# elm329.net
KiCad netlist of a schematic drawn in EAGLE
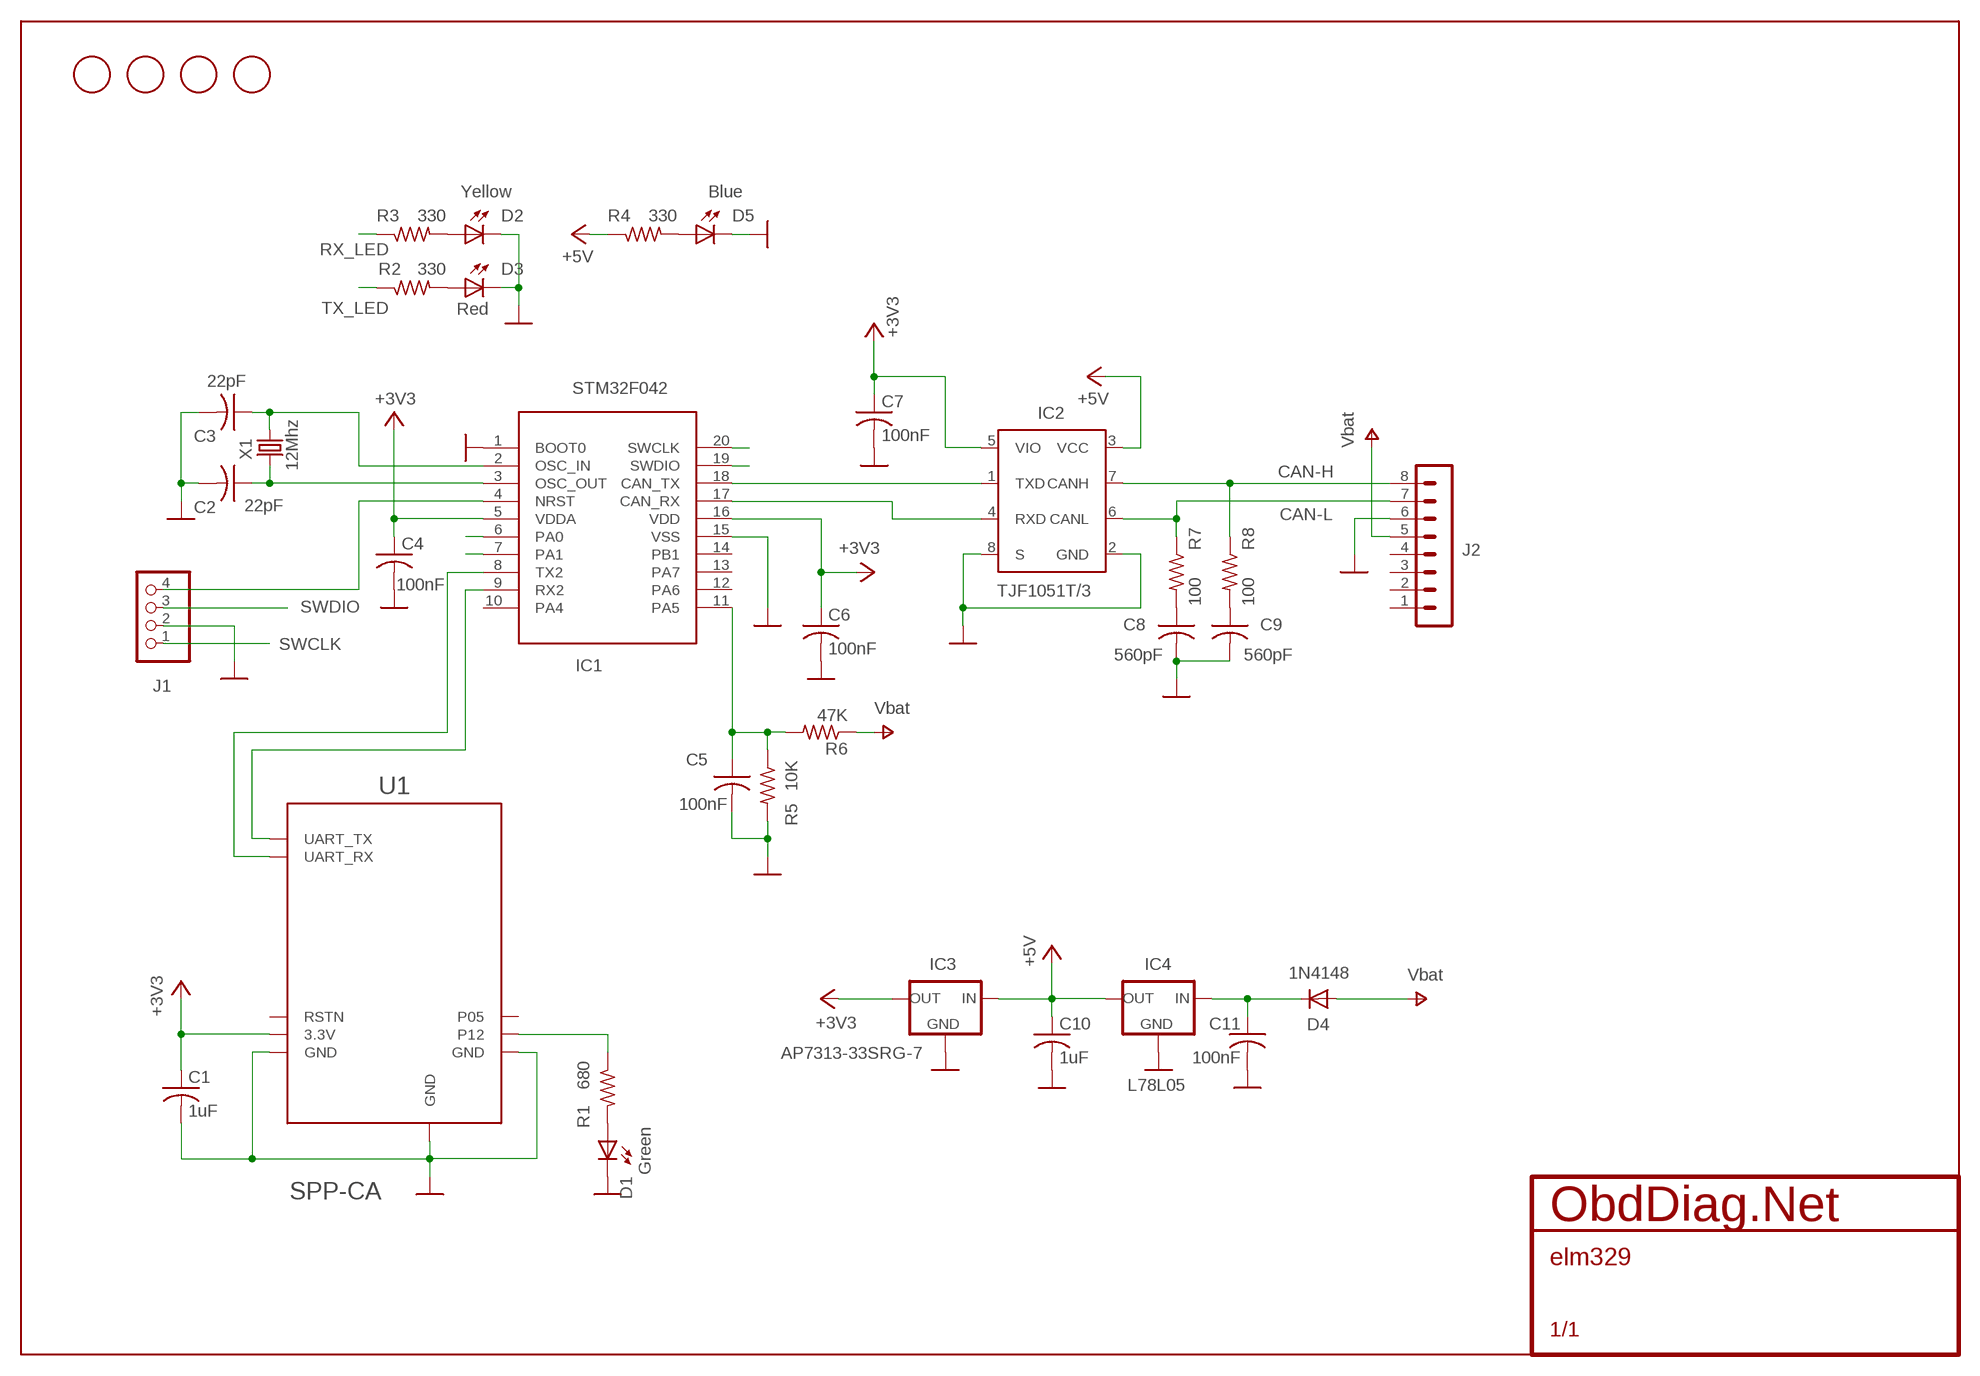
[diagram p0: schematic, sheet 1]

(export (version "E")
  (design (tool "Eeschema 10.0.6"))
  (components
    (comp (ref "C1")
      (value "1uF")
      (footprint "eagle-import:C0805")
      (libsource (lib "eagle-import") (part "C-USC0805"))
    )
    (comp (ref "C2")
      (value "22pF")
      (footprint "eagle-import:C0805")
      (libsource (lib "eagle-import") (part "C-USC0805"))
    )
    (comp (ref "C3")
      (value "22pF")
      (footprint "eagle-import:C0805")
      (libsource (lib "eagle-import") (part "C-USC0805"))
    )
    (comp (ref "C4")
      (value "100nF")
      (footprint "eagle-import:C0805")
      (libsource (lib "eagle-import") (part "C-USC0805"))
    )
    (comp (ref "C5")
      (value "100nF")
      (footprint "eagle-import:C0805")
      (libsource (lib "eagle-import") (part "C-USC0805"))
    )
    (comp (ref "C6")
      (value "100nF")
      (footprint "eagle-import:C0805")
      (libsource (lib "eagle-import") (part "C-USC0805"))
    )
    (comp (ref "C7")
      (value "100nF")
      (footprint "eagle-import:C0805")
      (libsource (lib "eagle-import") (part "C-USC0805"))
    )
    (comp (ref "C8")
      (value "560pF")
      (footprint "eagle-import:C0805")
      (libsource (lib "eagle-import") (part "C-USC0805"))
    )
    (comp (ref "C9")
      (value "560pF")
      (footprint "eagle-import:C0805")
      (libsource (lib "eagle-import") (part "C-USC0805"))
    )
    (comp (ref "C10")
      (value "1uF")
      (footprint "eagle-import:C0805")
      (libsource (lib "eagle-import") (part "C-USC0805"))
    )
    (comp (ref "C11")
      (value "100nF")
      (footprint "eagle-import:C0805")
      (libsource (lib "eagle-import") (part "C-USC0805"))
    )
    (comp (ref "D1")
      (value "Green")
      (footprint "eagle-import:CHIPLED_0805")
      (libsource (lib "eagle-import") (part "LEDCHIPLED_0805"))
    )
    (comp (ref "D2")
      (value "Yellow")
      (footprint "eagle-import:CHIPLED_0805")
      (libsource (lib "eagle-import") (part "LEDCHIPLED_0805"))
    )
    (comp (ref "D3")
      (value "Red")
      (footprint "eagle-import:CHIPLED_0805")
      (libsource (lib "eagle-import") (part "LEDCHIPLED_0805"))
    )
    (comp (ref "D4")
      (value "1N4148")
      (footprint "eagle-import:SOD123")
      (libsource (lib "eagle-import") (part "1N4148W"))
    )
    (comp (ref "D5")
      (value "Blue")
      (footprint "eagle-import:CHIPLED_0805")
      (libsource (lib "eagle-import") (part "LEDCHIPLED_0805"))
    )
    (comp (ref "IC1")
      (value "STM32F042")
      (footprint "eagle-import:TSSOP20")
      (libsource (lib "eagle-import") (part "STM32F042-TSSOP"))
    )
    (comp (ref "IC2")
      (value "TJF1051T/3")
      (footprint "eagle-import:SO-8")
      (libsource (lib "eagle-import") (part "TJF1051"))
    )
    (comp (ref "IC3")
      (value "AP7313-33SRG-7")
      (footprint "eagle-import:SOT23")
      (libsource (lib "eagle-import") (part "MCP1700-SOT23"))
    )
    (comp (ref "IC4")
      (value "L78L05")
      (footprint "eagle-import:SOT89R")
      (libsource (lib "eagle-import") (part "L78LXX-SOT89"))
    )
    (comp (ref "J1")
      (value "1X04")
      (footprint "eagle-import:1X04")
      (libsource (lib "eagle-import") (part "1X04SMALL"))
    )
    (comp (ref "J2")
      (value "MA08-1")
      (footprint "eagle-import:MA08-1")
      (libsource (lib "eagle-import") (part "MA08-1"))
    )
    (comp (ref "R1")
      (value "680")
      (footprint "eagle-import:R0805")
      (libsource (lib "eagle-import") (part "R-US_R0805"))
    )
    (comp (ref "R2")
      (value "330")
      (footprint "eagle-import:R0805")
      (libsource (lib "eagle-import") (part "R-US_R0805"))
    )
    (comp (ref "R3")
      (value "330")
      (footprint "eagle-import:R0805")
      (libsource (lib "eagle-import") (part "R-US_R0805"))
    )
    (comp (ref "R4")
      (value "330")
      (footprint "eagle-import:R0805")
      (libsource (lib "eagle-import") (part "R-US_R0805"))
    )
    (comp (ref "R5")
      (value "10K")
      (footprint "eagle-import:R0805")
      (libsource (lib "eagle-import") (part "R-US_R0805"))
    )
    (comp (ref "R6")
      (value "47K")
      (footprint "eagle-import:R0805")
      (libsource (lib "eagle-import") (part "R-US_R0805"))
    )
    (comp (ref "R7")
      (value "100")
      (footprint "eagle-import:R0805")
      (libsource (lib "eagle-import") (part "R-US_R0805"))
    )
    (comp (ref "R8")
      (value "100")
      (footprint "eagle-import:R0805")
      (libsource (lib "eagle-import") (part "R-US_R0805"))
    )
    (comp (ref "U$1")
      (value "FIDUCIAL")
      (footprint "eagle-import:FIDUCIAL_1MM")
      (libsource (lib "eagle-import") (part "FIDUCIAL"))
    )
    (comp (ref "U$2")
      (value "FIDUCIAL")
      (footprint "eagle-import:FIDUCIAL_1MM")
      (libsource (lib "eagle-import") (part "FIDUCIAL"))
    )
    (comp (ref "U$4")
      (value "FIDUCIAL")
      (footprint "eagle-import:FIDUCIAL_1MM")
      (libsource (lib "eagle-import") (part "FIDUCIAL"))
    )
    (comp (ref "U$5")
      (value "FIDUCIAL")
      (footprint "eagle-import:FIDUCIAL_1MM")
      (libsource (lib "eagle-import") (part "FIDUCIAL"))
    )
    (comp (ref "U1")
      (value "SPP-CA")
      (footprint "eagle-import:HM-10_16")
      (libsource (lib "eagle-import") (part "SPP-CA"))
    )
    (comp (ref "X1")
      (value "12Mhz")
      (footprint "eagle-import:SM49")
      (libsource (lib "eagle-import") (part "CRYSTALSM49"))
    )
  )
  (nets
    (net (code "1") (name "+3V3") (class "Default")
      (node (ref "C1") (pin "1") (pinfunction "1_1") (pintype "passive"))
      (node (ref "C4") (pin "1") (pinfunction "1_1") (pintype "passive"))
      (node (ref "C6") (pin "1") (pinfunction "1_1") (pintype "passive"))
      (node (ref "C7") (pin "1") (pinfunction "1_1") (pintype "passive"))
      (node (ref "IC1") (pin "16") (pinfunction "VDD_16") (pintype "power_in"))
      (node (ref "IC1") (pin "5") (pinfunction "VDDA_5") (pintype "power_in"))
      (node (ref "IC2") (pin "5") (pinfunction "VIO_5") (pintype "power_in"))
      (node (ref "IC3") (pin "2") (pinfunction "OUT_2") (pintype "passive"))
      (node (ref "U1") (pin "12") (pinfunction "3.3V_12") (pintype "power_in"))
    )
    (net (code "2") (name "+5V") (class "Default")
      (node (ref "C10") (pin "1") (pinfunction "1_1") (pintype "passive"))
      (node (ref "IC2") (pin "3") (pinfunction "VCC_3") (pintype "power_in"))
      (node (ref "IC3") (pin "3") (pinfunction "IN_3") (pintype "input"))
      (node (ref "IC4") (pin "2") (pinfunction "OUT_2") (pintype "passive"))
      (node (ref "R4") (pin "1") (pinfunction "1_1") (pintype "passive"))
    )
    (net (code "3") (name "/CAN-H") (class "Default")
      (node (ref "IC2") (pin "7") (pinfunction "CANH_7") (pintype "bidirectional"))
      (node (ref "J2") (pin "8") (pinfunction "8_8") (pintype "passive"))
      (node (ref "R8") (pin "1") (pinfunction "1_1") (pintype "passive"))
    )
    (net (code "4") (name "/CAN-L") (class "Default")
      (node (ref "IC2") (pin "6") (pinfunction "CANL_6") (pintype "bidirectional"))
      (node (ref "J2") (pin "7") (pinfunction "7_7") (pintype "passive"))
      (node (ref "R7") (pin "1") (pinfunction "1_1") (pintype "passive"))
    )
    (net (code "5") (name "/RX_LED") (class "Default")
      (node (ref "IC1") (pin "7") (pinfunction "PA1_7") (pintype "bidirectional"))
      (node (ref "R3") (pin "1") (pinfunction "1_1") (pintype "passive"))
    )
    (net (code "6") (name "/SWCLK") (class "Default")
      (node (ref "IC1") (pin "20") (pinfunction "SWCLK_20") (pintype "input"))
      (node (ref "J1") (pin "1") (pinfunction "1_1") (pintype "passive"))
    )
    (net (code "7") (name "/SWDIO") (class "Default")
      (node (ref "IC1") (pin "19") (pinfunction "SWDIO_19") (pintype "bidirectional"))
      (node (ref "J1") (pin "3") (pinfunction "3_3") (pintype "passive"))
    )
    (net (code "8") (name "/TX_LED") (class "Default")
      (node (ref "IC1") (pin "6") (pinfunction "PA0_6") (pintype "bidirectional"))
      (node (ref "R2") (pin "1") (pinfunction "1_1") (pintype "passive"))
    )
    (net (code "9") (name "GND") (class "Default")
      (node (ref "C1") (pin "2") (pinfunction "2_2") (pintype "passive"))
      (node (ref "C10") (pin "2") (pinfunction "2_2") (pintype "passive"))
      (node (ref "C11") (pin "2") (pinfunction "2_2") (pintype "passive"))
      (node (ref "C2") (pin "2") (pinfunction "2_2") (pintype "passive"))
      (node (ref "C3") (pin "2") (pinfunction "2_2") (pintype "passive"))
      (node (ref "C4") (pin "2") (pinfunction "2_2") (pintype "passive"))
      (node (ref "C5") (pin "2") (pinfunction "2_2") (pintype "passive"))
      (node (ref "C6") (pin "2") (pinfunction "2_2") (pintype "passive"))
      (node (ref "C7") (pin "2") (pinfunction "2_2") (pintype "passive"))
      (node (ref "C8") (pin "2") (pinfunction "2_2") (pintype "passive"))
      (node (ref "C9") (pin "2") (pinfunction "2_2") (pintype "passive"))
      (node (ref "D1") (pin "C") (pinfunction "C_C") (pintype "passive"))
      (node (ref "D2") (pin "C") (pinfunction "C_C") (pintype "passive"))
      (node (ref "D3") (pin "C") (pinfunction "C_C") (pintype "passive"))
      (node (ref "D5") (pin "C") (pinfunction "C_C") (pintype "passive"))
      (node (ref "IC1") (pin "1") (pinfunction "BOOT0_1") (pintype "bidirectional"))
      (node (ref "IC1") (pin "15") (pinfunction "VSS_15") (pintype "power_in"))
      (node (ref "IC2") (pin "2") (pinfunction "GND_2") (pintype "power_in"))
      (node (ref "IC2") (pin "8") (pinfunction "S_8") (pintype "input"))
      (node (ref "IC3") (pin "1") (pinfunction "GND_1") (pintype "input"))
      (node (ref "IC4") (pin "4") (pinfunction "GND_4") (pintype "input"))
      (node (ref "J1") (pin "2") (pinfunction "2_2") (pintype "passive"))
      (node (ref "J2") (pin "6") (pinfunction "6_6") (pintype "passive"))
      (node (ref "R5") (pin "2") (pinfunction "2_2") (pintype "passive"))
      (node (ref "U1") (pin "13") (pinfunction "GND_13") (pintype "power_in"))
      (node (ref "U1") (pin "21") (pinfunction "GND_21") (pintype "power_in"))
      (node (ref "U1") (pin "22") (pinfunction "GND_22") (pintype "power_in"))
    )
    (net (code "10") (name "Net-(C8-Pad1)") (class "Default")
      (node (ref "C8") (pin "1") (pinfunction "1_1") (pintype "passive"))
      (node (ref "R7") (pin "2") (pinfunction "2_2") (pintype "passive"))
    )
    (net (code "11") (name "Net-(C9-Pad1)") (class "Default")
      (node (ref "C9") (pin "1") (pinfunction "1_1") (pintype "passive"))
      (node (ref "R8") (pin "2") (pinfunction "2_2") (pintype "passive"))
    )
    (net (code "12") (name "Net-(D1-PadA)") (class "Default")
      (node (ref "D1") (pin "A") (pinfunction "A_A") (pintype "passive"))
      (node (ref "R1") (pin "2") (pinfunction "2_2") (pintype "passive"))
    )
    (net (code "13") (name "Net-(D2-PadA)") (class "Default")
      (node (ref "D2") (pin "A") (pinfunction "A_A") (pintype "passive"))
      (node (ref "R3") (pin "2") (pinfunction "2_2") (pintype "passive"))
    )
    (net (code "14") (name "Net-(D3-PadA)") (class "Default")
      (node (ref "D3") (pin "A") (pinfunction "A_A") (pintype "passive"))
      (node (ref "R2") (pin "2") (pinfunction "2_2") (pintype "passive"))
    )
    (net (code "15") (name "Net-(D5-PadA)") (class "Default")
      (node (ref "D5") (pin "A") (pinfunction "A_A") (pintype "passive"))
      (node (ref "R4") (pin "2") (pinfunction "2_2") (pintype "passive"))
    )
    (net (code "16") (name "Net-(IC1-CAN_RX)") (class "Default")
      (node (ref "IC1") (pin "17") (pinfunction "CAN_RX_17") (pintype "input"))
      (node (ref "IC2") (pin "4") (pinfunction "RXD_4") (pintype "output"))
    )
    (net (code "17") (name "Net-(IC1-CAN_TX)") (class "Default")
      (node (ref "IC1") (pin "18") (pinfunction "CAN_TX_18") (pintype "output"))
      (node (ref "IC2") (pin "1") (pinfunction "TXD_1") (pintype "input"))
    )
    (net (code "18") (name "Net-(IC1-NRST)") (class "Default")
      (node (ref "IC1") (pin "4") (pinfunction "NRST_4") (pintype "input"))
      (node (ref "J1") (pin "4") (pinfunction "4_4") (pintype "passive"))
    )
    (net (code "19") (name "Net-(IC1-OSC_IN)") (class "Default")
      (node (ref "C3") (pin "1") (pinfunction "1_1") (pintype "passive"))
      (node (ref "IC1") (pin "2") (pinfunction "OSC_IN_2") (pintype "passive"))
      (node (ref "X1") (pin "1") (pinfunction "1_1") (pintype "passive"))
    )
    (net (code "20") (name "Net-(IC1-OSC_OUT)") (class "Default")
      (node (ref "C2") (pin "1") (pinfunction "1_1") (pintype "passive"))
      (node (ref "IC1") (pin "3") (pinfunction "OSC_OUT_3") (pintype "passive"))
      (node (ref "X1") (pin "2") (pinfunction "2_2") (pintype "passive"))
    )
    (net (code "21") (name "Net-(IC1-PA5)") (class "Default")
      (node (ref "C5") (pin "1") (pinfunction "1_1") (pintype "passive"))
      (node (ref "IC1") (pin "11") (pinfunction "PA5_11") (pintype "bidirectional"))
      (node (ref "R5") (pin "1") (pinfunction "1_1") (pintype "passive"))
      (node (ref "R6") (pin "2") (pinfunction "2_2") (pintype "passive"))
    )
    (net (code "22") (name "Net-(IC1-RX2)") (class "Default")
      (node (ref "IC1") (pin "9") (pinfunction "RX2_9") (pintype "bidirectional"))
      (node (ref "U1") (pin "1") (pinfunction "UART_TX_1") (pintype "bidirectional"))
    )
    (net (code "23") (name "Net-(IC1-TX2)") (class "Default")
      (node (ref "IC1") (pin "8") (pinfunction "TX2_8") (pintype "bidirectional"))
      (node (ref "U1") (pin "2") (pinfunction "UART_RX_2") (pintype "bidirectional"))
    )
    (net (code "24") (name "Net-(IC4-IN)") (class "Default")
      (node (ref "C11") (pin "1") (pinfunction "1_1") (pintype "passive"))
      (node (ref "D4") (pin "C") (pinfunction "C_C") (pintype "passive"))
      (node (ref "IC4") (pin "1") (pinfunction "IN_1") (pintype "input"))
    )
    (net (code "25") (name "Net-(U1-P12)") (class "Default")
      (node (ref "R1") (pin "1") (pinfunction "1_1") (pintype "passive"))
      (node (ref "U1") (pin "24") (pinfunction "P12_24") (pintype "bidirectional"))
    )
    (net (code "26") (name "Vbat") (class "Default")
      (node (ref "D4") (pin "A") (pinfunction "A_A") (pintype "passive"))
      (node (ref "J2") (pin "5") (pinfunction "5_5") (pintype "passive"))
      (node (ref "R6") (pin "1") (pinfunction "1_1") (pintype "passive"))
    )
    (net (code "27") (name "unconnected-(IC1-PA4-Pad10)") (class "Default")
      (node (ref "IC1") (pin "10") (pinfunction "PA4_10") (pintype "bidirectional"))
    )
    (net (code "28") (name "unconnected-(IC1-PA6-Pad12)") (class "Default")
      (node (ref "IC1") (pin "12") (pinfunction "PA6_12") (pintype "bidirectional"))
    )
    (net (code "29") (name "unconnected-(IC1-PA7-Pad13)") (class "Default")
      (node (ref "IC1") (pin "13") (pinfunction "PA7_13") (pintype "bidirectional"))
    )
    (net (code "30") (name "unconnected-(IC1-PB1-Pad14)") (class "Default")
      (node (ref "IC1") (pin "14") (pinfunction "PB1_14") (pintype "bidirectional"))
    )
    (net (code "31") (name "unconnected-(J2-Pad1)") (class "Default")
      (node (ref "J2") (pin "1") (pinfunction "1_1") (pintype "passive"))
    )
    (net (code "32") (name "unconnected-(J2-Pad2)") (class "Default")
      (node (ref "J2") (pin "2") (pinfunction "2_2") (pintype "passive"))
    )
    (net (code "33") (name "unconnected-(J2-Pad3)") (class "Default")
      (node (ref "J2") (pin "3") (pinfunction "3_3") (pintype "passive"))
    )
    (net (code "34") (name "unconnected-(J2-Pad4)") (class "Default")
      (node (ref "J2") (pin "4") (pinfunction "4_4") (pintype "passive"))
    )
    (net (code "35") (name "unconnected-(U1-P05-Pad25)") (class "Default")
      (node (ref "U1") (pin "25") (pinfunction "P05_25") (pintype "bidirectional"))
    )
    (net (code "36") (name "unconnected-(U1-RSTN-Pad11)") (class "Default")
      (node (ref "U1") (pin "11") (pinfunction "RSTN_11") (pintype "input"))
    )
  )
)
